# Battery_board.net
KiCad netlist of a schematic drawn in EAGLE
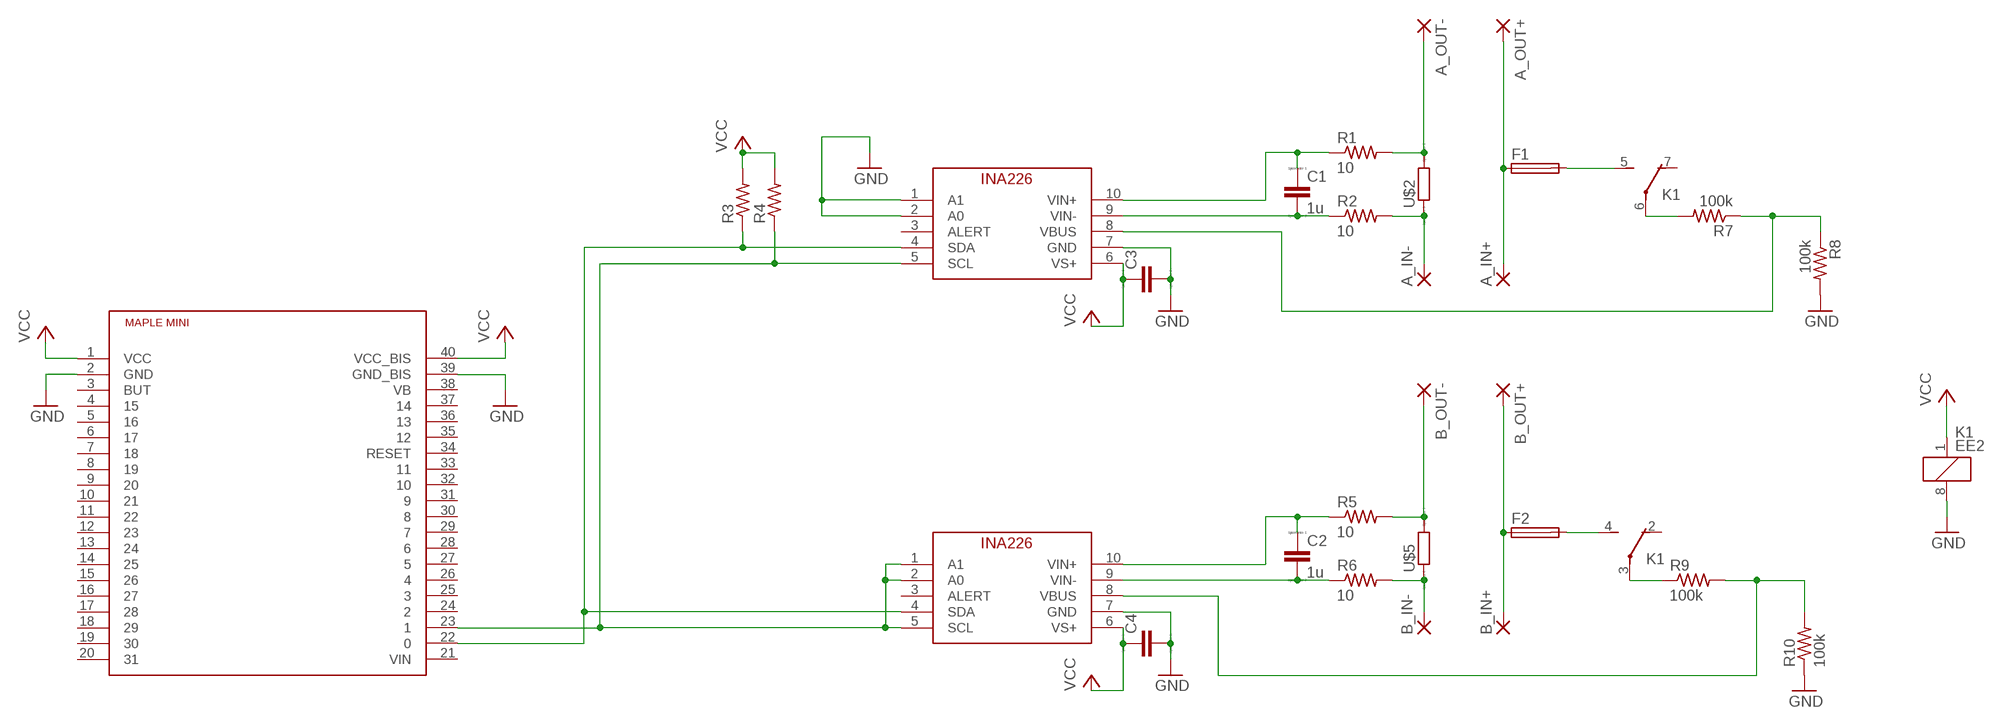
[diagram p0: schematic, sheet 1]

(export (version "E")
  (design (tool "Eeschema 10.0.6"))
  (components
    (comp (ref "A_IN+")
      (value "WIREPAD4,16O1,6")
      (footprint "eagle-import:4,16O1,6")
      (libsource (lib "eagle-import") (part "WIREPAD4,16O1,6"))
    )
    (comp (ref "A_IN-")
      (value "WIREPAD4,16O1,6")
      (footprint "eagle-import:4,16O1,6")
      (libsource (lib "eagle-import") (part "WIREPAD4,16O1,6"))
    )
    (comp (ref "A_OUT+")
      (value "WIREPAD4,16O1,6")
      (footprint "eagle-import:4,16O1,6")
      (libsource (lib "eagle-import") (part "WIREPAD4,16O1,6"))
    )
    (comp (ref "A_OUT-")
      (value "WIREPAD4,16O1,6")
      (footprint "eagle-import:4,16O1,6")
      (libsource (lib "eagle-import") (part "WIREPAD4,16O1,6"))
    )
    (comp (ref "B_IN+")
      (value "WIREPAD4,16O1,6")
      (footprint "eagle-import:4,16O1,6")
      (libsource (lib "eagle-import") (part "WIREPAD4,16O1,6"))
    )
    (comp (ref "B_IN-")
      (value "WIREPAD4,16O1,6")
      (footprint "eagle-import:4,16O1,6")
      (libsource (lib "eagle-import") (part "WIREPAD4,16O1,6"))
    )
    (comp (ref "B_OUT+")
      (value "WIREPAD4,16O1,6")
      (footprint "eagle-import:4,16O1,6")
      (libsource (lib "eagle-import") (part "WIREPAD4,16O1,6"))
    )
    (comp (ref "B_OUT-")
      (value "WIREPAD4,16O1,6")
      (footprint "eagle-import:4,16O1,6")
      (libsource (lib "eagle-import") (part "WIREPAD4,16O1,6"))
    )
    (comp (ref "C1")
      (value "1u")
      (footprint "eagle-import:C0603")
      (libsource (lib "eagle-import") (part "CC0603"))
    )
    (comp (ref "C2")
      (value "1u")
      (footprint "eagle-import:C0603")
      (libsource (lib "eagle-import") (part "CC0603"))
    )
    (comp (ref "C3")
      (value "CC0603")
      (footprint "eagle-import:C0603")
      (libsource (lib "eagle-import") (part "CC0603"))
    )
    (comp (ref "C4")
      (value "CC0603")
      (footprint "eagle-import:C0603")
      (libsource (lib "eagle-import") (part "CC0603"))
    )
    (comp (ref "F1")
      (value "TE5")
      (footprint "eagle-import:TE5")
      (libsource (lib "eagle-import") (part "TE5"))
    )
    (comp (ref "F2")
      (value "TE5")
      (footprint "eagle-import:TE5")
      (libsource (lib "eagle-import") (part "TE5"))
    )
    (comp (ref "K1")
      (value "EE2")
      (footprint "eagle-import:EE2-5NU")
      (libsource (lib "eagle-import") (part "EE2"))
    )
    (comp (ref "R1")
      (value "10")
      (footprint "eagle-import:R0603")
      (libsource (lib "eagle-import") (part "R-US_R0603"))
    )
    (comp (ref "R2")
      (value "10")
      (footprint "eagle-import:R0603")
      (libsource (lib "eagle-import") (part "R-US_R0603"))
    )
    (comp (ref "R3")
      (value "R-US_R0603")
      (footprint "eagle-import:R0603")
      (libsource (lib "eagle-import") (part "R-US_R0603"))
    )
    (comp (ref "R4")
      (value "R-US_R0603")
      (footprint "eagle-import:R0603")
      (libsource (lib "eagle-import") (part "R-US_R0603"))
    )
    (comp (ref "R5")
      (value "10")
      (footprint "eagle-import:R0603")
      (libsource (lib "eagle-import") (part "R-US_R0603"))
    )
    (comp (ref "R6")
      (value "10")
      (footprint "eagle-import:R0603")
      (libsource (lib "eagle-import") (part "R-US_R0603"))
    )
    (comp (ref "R7")
      (value "100k")
      (footprint "eagle-import:R1206")
      (libsource (lib "eagle-import") (part "R-US_R1206"))
    )
    (comp (ref "R8")
      (value "100k")
      (footprint "eagle-import:R1206")
      (libsource (lib "eagle-import") (part "R-US_R1206"))
    )
    (comp (ref "R9")
      (value "100k")
      (footprint "eagle-import:R1206")
      (libsource (lib "eagle-import") (part "R-US_R1206"))
    )
    (comp (ref "R10")
      (value "100k")
      (footprint "eagle-import:R1206")
      (libsource (lib "eagle-import") (part "R-US_R1206"))
    )
    (comp (ref "U$1")
      (value "INA226")
      (footprint "eagle-import:MSOP10")
      (libsource (lib "eagle-import") (part "INA226"))
    )
    (comp (ref "U$2")
      (value "R_SHUNT_2526")
      (footprint "eagle-import:R2526")
      (libsource (lib "eagle-import") (part "R_SHUNT_2526"))
    )
    (comp (ref "U$3")
      (value "MAPLE_MINI")
      (footprint "eagle-import:DIL40_MAPLE")
      (libsource (lib "eagle-import") (part "MAPLE_MINI"))
    )
    (comp (ref "U$4")
      (value "INA226")
      (footprint "eagle-import:MSOP10")
      (libsource (lib "eagle-import") (part "INA226"))
    )
    (comp (ref "U$5")
      (value "R_SHUNT_2526")
      (footprint "eagle-import:R2526")
      (libsource (lib "eagle-import") (part "R_SHUNT_2526"))
    )
  )
  (nets
    (net (code "1") (name "GND") (class "Default")
      (node (ref "C3") (pin "2") (pinfunction "2_2") (pintype "passive"))
      (node (ref "C4") (pin "2") (pinfunction "2_2") (pintype "passive"))
      (node (ref "K1") (pin "8") (pinfunction "2_8") (pintype "passive"))
      (node (ref "R10") (pin "1") (pinfunction "1_1") (pintype "passive"))
      (node (ref "R8") (pin "2") (pinfunction "2_2") (pintype "passive"))
      (node (ref "U$1") (pin "1") (pinfunction "A1_1") (pintype "bidirectional"))
      (node (ref "U$1") (pin "2") (pinfunction "A0_2") (pintype "bidirectional"))
      (node (ref "U$1") (pin "7") (pinfunction "GND_7") (pintype "bidirectional"))
      (node (ref "U$3") (pin "2") (pinfunction "GND_2") (pintype "bidirectional"))
      (node (ref "U$3") (pin "39") (pinfunction "GND_BIS_39") (pintype "bidirectional"))
      (node (ref "U$4") (pin "7") (pinfunction "GND_7") (pintype "bidirectional"))
    )
    (net (code "2") (name "Net-(A_IN+-P)") (class "Default")
      (node (ref "A_IN+") (pin "1") (pinfunction "P_1") (pintype "passive"))
      (node (ref "A_OUT+") (pin "1") (pinfunction "P_1") (pintype "passive"))
      (node (ref "F1") (pin "1") (pinfunction "1_1") (pintype "passive"))
    )
    (net (code "3") (name "Net-(A_IN--P)") (class "Default")
      (node (ref "A_IN-") (pin "1") (pinfunction "P_1") (pintype "passive"))
      (node (ref "R2") (pin "2") (pinfunction "2_2") (pintype "passive"))
      (node (ref "U$2") (pin "1") (pinfunction "1_1") (pintype "passive"))
    )
    (net (code "4") (name "Net-(A_OUT--P)") (class "Default")
      (node (ref "A_OUT-") (pin "1") (pinfunction "P_1") (pintype "passive"))
      (node (ref "R1") (pin "2") (pinfunction "2_2") (pintype "passive"))
      (node (ref "U$2") (pin "2") (pinfunction "2_2") (pintype "passive"))
    )
    (net (code "5") (name "Net-(B_IN+-P)") (class "Default")
      (node (ref "B_IN+") (pin "1") (pinfunction "P_1") (pintype "passive"))
      (node (ref "B_OUT+") (pin "1") (pinfunction "P_1") (pintype "passive"))
      (node (ref "F2") (pin "1") (pinfunction "1_1") (pintype "passive"))
    )
    (net (code "6") (name "Net-(B_IN--P)") (class "Default")
      (node (ref "B_IN-") (pin "1") (pinfunction "P_1") (pintype "passive"))
      (node (ref "R6") (pin "2") (pinfunction "2_2") (pintype "passive"))
      (node (ref "U$5") (pin "1") (pinfunction "1_1") (pintype "passive"))
    )
    (net (code "7") (name "Net-(B_OUT--P)") (class "Default")
      (node (ref "B_OUT-") (pin "1") (pinfunction "P_1") (pintype "passive"))
      (node (ref "R5") (pin "2") (pinfunction "2_2") (pintype "passive"))
      (node (ref "U$5") (pin "2") (pinfunction "2_2") (pintype "passive"))
    )
    (net (code "8") (name "Net-(K1B-P)") (class "Default")
      (node (ref "K1") (pin "3") (pinfunction "P_3") (pintype "passive"))
      (node (ref "R9") (pin "1") (pinfunction "1_1") (pintype "passive"))
    )
    (net (code "9") (name "Net-(K1B-S)") (class "Default")
      (node (ref "F2") (pin "2") (pinfunction "2_2") (pintype "passive"))
      (node (ref "K1") (pin "4") (pinfunction "S_4") (pintype "passive"))
    )
    (net (code "10") (name "Net-(K1C-P)") (class "Default")
      (node (ref "K1") (pin "6") (pinfunction "P_6") (pintype "passive"))
      (node (ref "R7") (pin "2") (pinfunction "2_2") (pintype "passive"))
    )
    (net (code "11") (name "Net-(K1C-S)") (class "Default")
      (node (ref "F1") (pin "2") (pinfunction "2_2") (pintype "passive"))
      (node (ref "K1") (pin "5") (pinfunction "S_5") (pintype "passive"))
    )
    (net (code "12") (name "Net-(U$1-SCL)") (class "Default")
      (node (ref "R4") (pin "1") (pinfunction "1_1") (pintype "passive"))
      (node (ref "U$1") (pin "5") (pinfunction "SCL_5") (pintype "bidirectional"))
      (node (ref "U$3") (pin "23") (pinfunction "1_23") (pintype "bidirectional"))
      (node (ref "U$4") (pin "1") (pinfunction "A1_1") (pintype "bidirectional"))
      (node (ref "U$4") (pin "2") (pinfunction "A0_2") (pintype "bidirectional"))
      (node (ref "U$4") (pin "5") (pinfunction "SCL_5") (pintype "bidirectional"))
    )
    (net (code "13") (name "Net-(U$1-SDA)") (class "Default")
      (node (ref "R3") (pin "1") (pinfunction "1_1") (pintype "passive"))
      (node (ref "U$1") (pin "4") (pinfunction "SDA_4") (pintype "bidirectional"))
      (node (ref "U$3") (pin "22") (pinfunction "0_22") (pintype "bidirectional"))
      (node (ref "U$4") (pin "4") (pinfunction "SDA_4") (pintype "bidirectional"))
    )
    (net (code "14") (name "Net-(U$1-VBUS)") (class "Default")
      (node (ref "R7") (pin "1") (pinfunction "1_1") (pintype "passive"))
      (node (ref "R8") (pin "1") (pinfunction "1_1") (pintype "passive"))
      (node (ref "U$1") (pin "8") (pinfunction "VBUS_8") (pintype "bidirectional"))
    )
    (net (code "15") (name "Net-(U$1-VIN+)") (class "Default")
      (node (ref "C1") (pin "1") (pinfunction "1_1") (pintype "passive"))
      (node (ref "R1") (pin "1") (pinfunction "1_1") (pintype "passive"))
      (node (ref "U$1") (pin "10") (pinfunction "VIN+_10") (pintype "bidirectional"))
    )
    (net (code "16") (name "Net-(U$1-VIN-)") (class "Default")
      (node (ref "C1") (pin "2") (pinfunction "2_2") (pintype "passive"))
      (node (ref "R2") (pin "1") (pinfunction "1_1") (pintype "passive"))
      (node (ref "U$1") (pin "9") (pinfunction "VIN-_9") (pintype "bidirectional"))
    )
    (net (code "17") (name "Net-(U$4-VBUS)") (class "Default")
      (node (ref "R10") (pin "2") (pinfunction "2_2") (pintype "passive"))
      (node (ref "R9") (pin "2") (pinfunction "2_2") (pintype "passive"))
      (node (ref "U$4") (pin "8") (pinfunction "VBUS_8") (pintype "bidirectional"))
    )
    (net (code "18") (name "Net-(U$4-VIN+)") (class "Default")
      (node (ref "C2") (pin "1") (pinfunction "1_1") (pintype "passive"))
      (node (ref "R5") (pin "1") (pinfunction "1_1") (pintype "passive"))
      (node (ref "U$4") (pin "10") (pinfunction "VIN+_10") (pintype "bidirectional"))
    )
    (net (code "19") (name "Net-(U$4-VIN-)") (class "Default")
      (node (ref "C2") (pin "2") (pinfunction "2_2") (pintype "passive"))
      (node (ref "R6") (pin "1") (pinfunction "1_1") (pintype "passive"))
      (node (ref "U$4") (pin "9") (pinfunction "VIN-_9") (pintype "bidirectional"))
    )
    (net (code "20") (name "VCC") (class "Default")
      (node (ref "C3") (pin "1") (pinfunction "1_1") (pintype "passive"))
      (node (ref "C4") (pin "1") (pinfunction "1_1") (pintype "passive"))
      (node (ref "K1") (pin "1") (pinfunction "1_1") (pintype "passive"))
      (node (ref "R3") (pin "2") (pinfunction "2_2") (pintype "passive"))
      (node (ref "R4") (pin "2") (pinfunction "2_2") (pintype "passive"))
      (node (ref "U$1") (pin "6") (pinfunction "VS+_6") (pintype "bidirectional"))
      (node (ref "U$3") (pin "1") (pinfunction "VCC_1") (pintype "bidirectional"))
      (node (ref "U$3") (pin "40") (pinfunction "VCC_BIS_40") (pintype "bidirectional"))
      (node (ref "U$4") (pin "6") (pinfunction "VS+_6") (pintype "bidirectional"))
    )
    (net (code "21") (name "unconnected-(K1B-O-Pad2)") (class "Default")
      (node (ref "K1") (pin "2") (pinfunction "O_2") (pintype "passive"))
    )
    (net (code "22") (name "unconnected-(K1C-O-Pad7)") (class "Default")
      (node (ref "K1") (pin "7") (pinfunction "O_7") (pintype "passive"))
    )
    (net (code "23") (name "unconnected-(U$1-ALERT-Pad3)") (class "Default")
      (node (ref "U$1") (pin "3") (pinfunction "ALERT_3") (pintype "bidirectional"))
    )
    (net (code "24") (name "unconnected-(U$3-2-Pad24)") (class "Default")
      (node (ref "U$3") (pin "24") (pinfunction "2_24") (pintype "bidirectional"))
    )
    (net (code "25") (name "unconnected-(U$3-3-Pad25)") (class "Default")
      (node (ref "U$3") (pin "25") (pinfunction "3_25") (pintype "bidirectional"))
    )
    (net (code "26") (name "unconnected-(U$3-4-Pad26)") (class "Default")
      (node (ref "U$3") (pin "26") (pinfunction "4_26") (pintype "bidirectional"))
    )
    (net (code "27") (name "unconnected-(U$3-5-Pad27)") (class "Default")
      (node (ref "U$3") (pin "27") (pinfunction "5_27") (pintype "bidirectional"))
    )
    (net (code "28") (name "unconnected-(U$3-6-Pad28)") (class "Default")
      (node (ref "U$3") (pin "28") (pinfunction "6_28") (pintype "bidirectional"))
    )
    (net (code "29") (name "unconnected-(U$3-7-Pad29)") (class "Default")
      (node (ref "U$3") (pin "29") (pinfunction "7_29") (pintype "bidirectional"))
    )
    (net (code "30") (name "unconnected-(U$3-8-Pad30)") (class "Default")
      (node (ref "U$3") (pin "30") (pinfunction "8_30") (pintype "bidirectional"))
    )
    (net (code "31") (name "unconnected-(U$3-9-Pad31)") (class "Default")
      (node (ref "U$3") (pin "31") (pinfunction "9_31") (pintype "bidirectional"))
    )
    (net (code "32") (name "unconnected-(U$3-10-Pad32)") (class "Default")
      (node (ref "U$3") (pin "32") (pinfunction "10_32") (pintype "bidirectional"))
    )
    (net (code "33") (name "unconnected-(U$3-11-Pad33)") (class "Default")
      (node (ref "U$3") (pin "33") (pinfunction "11_33") (pintype "bidirectional"))
    )
    (net (code "34") (name "unconnected-(U$3-12-Pad35)") (class "Default")
      (node (ref "U$3") (pin "35") (pinfunction "12_35") (pintype "bidirectional"))
    )
    (net (code "35") (name "unconnected-(U$3-13-Pad36)") (class "Default")
      (node (ref "U$3") (pin "36") (pinfunction "13_36") (pintype "bidirectional"))
    )
    (net (code "36") (name "unconnected-(U$3-14-Pad37)") (class "Default")
      (node (ref "U$3") (pin "37") (pinfunction "14_37") (pintype "bidirectional"))
    )
    (net (code "37") (name "unconnected-(U$3-15-Pad4)") (class "Default")
      (node (ref "U$3") (pin "4") (pinfunction "15_4") (pintype "bidirectional"))
    )
    (net (code "38") (name "unconnected-(U$3-16-Pad5)") (class "Default")
      (node (ref "U$3") (pin "5") (pinfunction "16_5") (pintype "bidirectional"))
    )
    (net (code "39") (name "unconnected-(U$3-17-Pad6)") (class "Default")
      (node (ref "U$3") (pin "6") (pinfunction "17_6") (pintype "bidirectional"))
    )
    (net (code "40") (name "unconnected-(U$3-18-Pad7)") (class "Default")
      (node (ref "U$3") (pin "7") (pinfunction "18_7") (pintype "bidirectional"))
    )
    (net (code "41") (name "unconnected-(U$3-19-Pad8)") (class "Default")
      (node (ref "U$3") (pin "8") (pinfunction "19_8") (pintype "bidirectional"))
    )
    (net (code "42") (name "unconnected-(U$3-20-Pad9)") (class "Default")
      (node (ref "U$3") (pin "9") (pinfunction "20_9") (pintype "bidirectional"))
    )
    (net (code "43") (name "unconnected-(U$3-21-Pad10)") (class "Default")
      (node (ref "U$3") (pin "10") (pinfunction "21_10") (pintype "bidirectional"))
    )
    (net (code "44") (name "unconnected-(U$3-22-Pad11)") (class "Default")
      (node (ref "U$3") (pin "11") (pinfunction "22_11") (pintype "bidirectional"))
    )
    (net (code "45") (name "unconnected-(U$3-23-Pad12)") (class "Default")
      (node (ref "U$3") (pin "12") (pinfunction "23_12") (pintype "bidirectional"))
    )
    (net (code "46") (name "unconnected-(U$3-24-Pad13)") (class "Default")
      (node (ref "U$3") (pin "13") (pinfunction "24_13") (pintype "bidirectional"))
    )
    (net (code "47") (name "unconnected-(U$3-25-Pad14)") (class "Default")
      (node (ref "U$3") (pin "14") (pinfunction "25_14") (pintype "bidirectional"))
    )
    (net (code "48") (name "unconnected-(U$3-26-Pad15)") (class "Default")
      (node (ref "U$3") (pin "15") (pinfunction "26_15") (pintype "bidirectional"))
    )
    (net (code "49") (name "unconnected-(U$3-27-Pad16)") (class "Default")
      (node (ref "U$3") (pin "16") (pinfunction "27_16") (pintype "bidirectional"))
    )
    (net (code "50") (name "unconnected-(U$3-28-Pad17)") (class "Default")
      (node (ref "U$3") (pin "17") (pinfunction "28_17") (pintype "bidirectional"))
    )
    (net (code "51") (name "unconnected-(U$3-29-Pad18)") (class "Default")
      (node (ref "U$3") (pin "18") (pinfunction "29_18") (pintype "bidirectional"))
    )
    (net (code "52") (name "unconnected-(U$3-30-Pad19)") (class "Default")
      (node (ref "U$3") (pin "19") (pinfunction "30_19") (pintype "bidirectional"))
    )
    (net (code "53") (name "unconnected-(U$3-31-Pad20)") (class "Default")
      (node (ref "U$3") (pin "20") (pinfunction "31_20") (pintype "bidirectional"))
    )
    (net (code "54") (name "unconnected-(U$3-BUT-Pad3)") (class "Default")
      (node (ref "U$3") (pin "3") (pinfunction "BUT_3") (pintype "bidirectional"))
    )
    (net (code "55") (name "unconnected-(U$3-RESET-Pad34)") (class "Default")
      (node (ref "U$3") (pin "34") (pinfunction "RESET_34") (pintype "bidirectional"))
    )
    (net (code "56") (name "unconnected-(U$3-VB-Pad38)") (class "Default")
      (node (ref "U$3") (pin "38") (pinfunction "VB_38") (pintype "bidirectional"))
    )
    (net (code "57") (name "unconnected-(U$3-VIN-Pad21)") (class "Default")
      (node (ref "U$3") (pin "21") (pinfunction "VIN_21") (pintype "bidirectional"))
    )
    (net (code "58") (name "unconnected-(U$4-ALERT-Pad3)") (class "Default")
      (node (ref "U$4") (pin "3") (pinfunction "ALERT_3") (pintype "bidirectional"))
    )
  )
)
